# AnemometroWifi.net
KiCad netlist of a schematic drawn in EAGLE
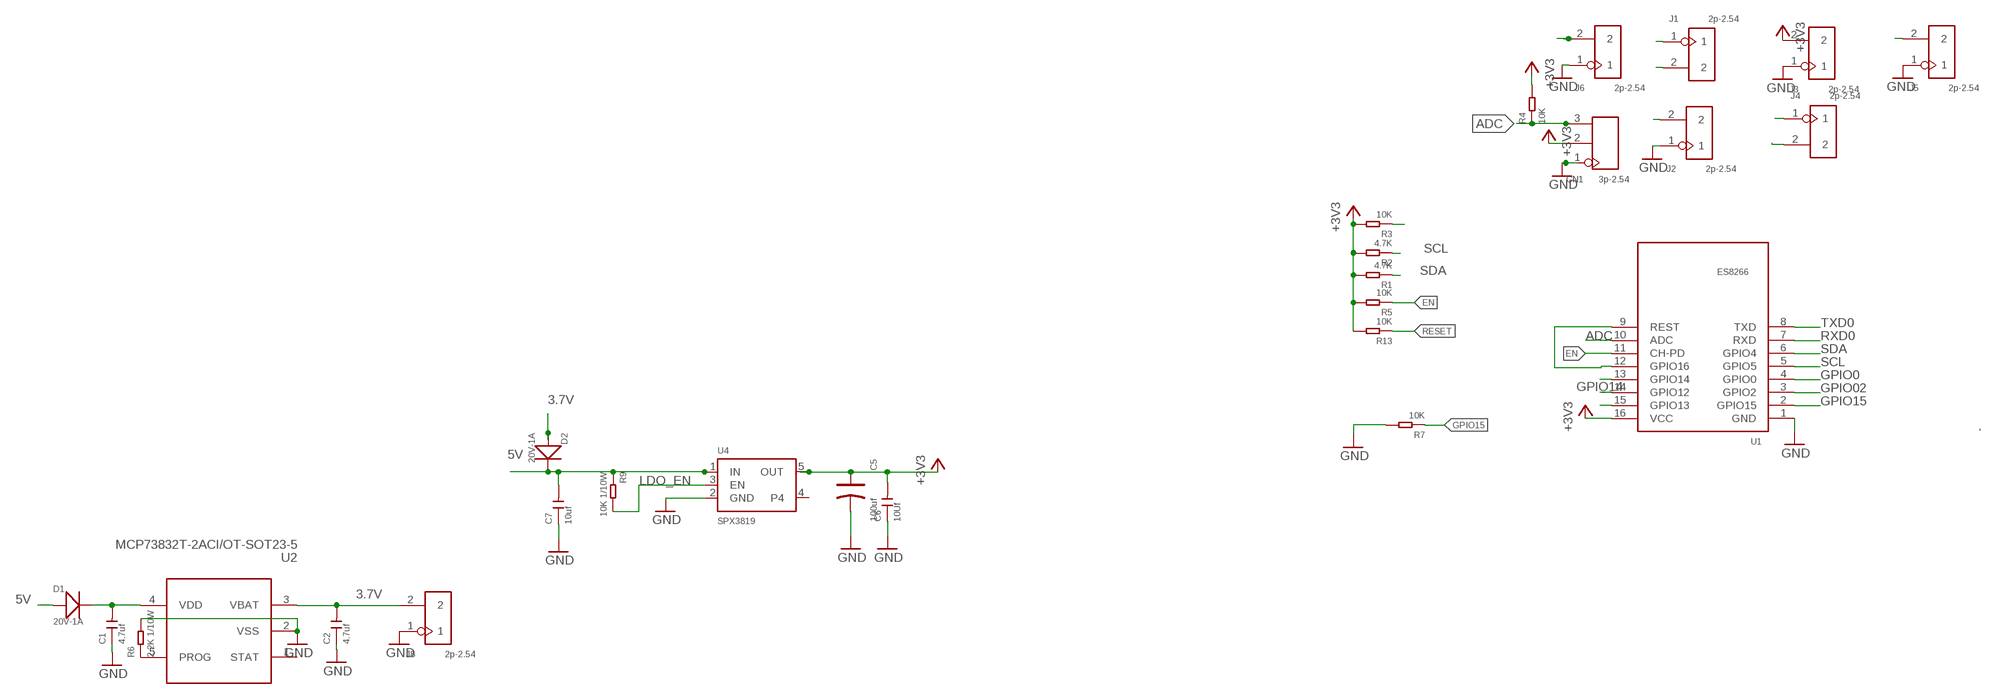
[diagram p0: schematic, sheet 1]

(export (version "E")
  (design (tool "Eeschema 10.0.6"))
  (components
    (comp (ref "C1")
      (value "4.7uf")
      (footprint "eagle-import:C0603")
      (fields (field (name "MPN") "CC0603KRX5R6BB475"))
      (libsource (lib "eagle-import") (part "CERAMIC-4.7UF-10V-10%-X5R(0603)"))
    )
    (comp (ref "C2")
      (value "4.7uf")
      (footprint "eagle-import:C0603")
      (fields (field (name "MPN") "CC0603KRX5R6BB475"))
      (libsource (lib "eagle-import") (part "CERAMIC-4.7UF-10V-10%-X5R(0603)"))
    )
    (comp (ref "C5")
      (value "100uf")
      (footprint "eagle-import:AVX-B")
      (fields (field (name "MPN") "TAJB107M010#NJ"))
      (libsource (lib "eagle-import") (part "TANTALUM-SMD-100UF-10V(AVX-B)"))
    )
    (comp (ref "C6")
      (value "10Uf")
      (footprint "eagle-import:C0603")
      (fields (field (name "MPN") "CC0603KRX7R9BB104"))
      (libsource (lib "eagle-import") (part "CERAMIC-100NF-50V-10%-X7R(0603)"))
    )
    (comp (ref "C7")
      (value "10uf")
      (footprint "eagle-import:C0805")
      (fields (field (name "MPN") "CC0805KKX5R8BB106"))
      (libsource (lib "eagle-import") (part "CERAMIC-10UF-25V-10%-X5R(0805)"))
    )
    (comp (ref "CN1")
      (value "3p-2.54")
      (footprint "eagle-import:H3-2.54")
      (libsource (lib "eagle-import") (part "DIP-BLACK-MALE-HEADER-VERT(3P-2.54)"))
    )
    (comp (ref "D1")
      (value "20V-1A")
      (footprint "eagle-import:SOD-123")
      (fields (field (name "MPN") "B5819W"))
      (libsource (lib "eagle-import") (part "SMD-DIODE-SCHOTTKY-20V-1A(SOD-123)"))
    )
    (comp (ref "D2")
      (value "20V-1A")
      (footprint "eagle-import:SOD-123")
      (fields (field (name "MPN") "B5819W"))
      (libsource (lib "eagle-import") (part "SMD-DIODE-SCHOTTKY-20V-1A(SOD-123)"))
    )
    (comp (ref "J1")
      (value "2p-2.54")
      (footprint "eagle-import:H2-2.54")
      (fields (field (name "MPN") "F185-1102A1BSYA1"))
      (libsource (lib "eagle-import") (part "DIP-BLACK-FEMALE-HEADER-VERT(2P-2.54)"))
    )
    (comp (ref "J2")
      (value "2p-2.54")
      (footprint "eagle-import:H2-2.54")
      (fields (field (name "MPN") "F185-1102A1BSYA1"))
      (libsource (lib "eagle-import") (part "DIP-BLACK-FEMALE-HEADER-VERT(2P-2.54)"))
    )
    (comp (ref "J3")
      (value "2p-2.54")
      (footprint "eagle-import:H2-2.54")
      (fields (field (name "MPN") "F185-1102A1BSYA1"))
      (libsource (lib "eagle-import") (part "DIP-BLACK-FEMALE-HEADER-VERT(2P-2.54)"))
    )
    (comp (ref "J4")
      (value "2p-2.54")
      (footprint "eagle-import:H2-2.54")
      (fields (field (name "MPN") "F185-1102A1BSYA1"))
      (libsource (lib "eagle-import") (part "DIP-BLACK-FEMALE-HEADER-VERT(2P-2.54)"))
    )
    (comp (ref "J5")
      (value "2p-2.54")
      (footprint "eagle-import:H2-2.54")
      (fields (field (name "MPN") "F185-1102A1BSYA1"))
      (libsource (lib "eagle-import") (part "DIP-BLACK-FEMALE-HEADER-VERT(2P-2.54)"))
    )
    (comp (ref "J6")
      (value "2p-2.54")
      (footprint "eagle-import:H2-2.54")
      (fields (field (name "MPN") "P125-1102A0BS116A1"))
      (libsource (lib "eagle-import") (part "DIP-BLACK-MALE-HEADER-VERT(2P-2.54)"))
    )
    (comp (ref "J8")
      (value "2p-2.54")
      (footprint "eagle-import:H2-2.54")
      (fields (field (name "MPN") "F185-1102A1BSYA1"))
      (libsource (lib "eagle-import") (part "DIP-BLACK-FEMALE-HEADER-VERT(2P-2.54)"))
    )
    (comp (ref "R1")
      (value "4.7K")
      (footprint "eagle-import:R0603")
      (fields (field (name "MPN") "RC0603JR-074K7L"))
      (libsource (lib "eagle-import") (part "SMD-RES-4.7K-5%-1/10W(0603)"))
    )
    (comp (ref "R2")
      (value "4.7K")
      (footprint "eagle-import:R0603")
      (fields (field (name "MPN") "RC0603JR-074K7L"))
      (libsource (lib "eagle-import") (part "SMD-RES-4.7K-5%-1/10W(0603)"))
    )
    (comp (ref "R3")
      (value "10K")
      (footprint "eagle-import:R0603")
      (fields (field (name "MPN") "RC0603JR-070RL"))
      (libsource (lib "eagle-import") (part "SMD-RES-0R-5%-1/10W(0603)"))
    )
    (comp (ref "R4")
      (value "10K")
      (footprint "eagle-import:R0603")
      (fields (field (name "MPN") "RC0603JR-070RL"))
      (libsource (lib "eagle-import") (part "SMD-RES-0R-5%-1/10W(0603)"))
    )
    (comp (ref "R5")
      (value "10K")
      (footprint "eagle-import:R0603")
      (fields (field (name "MPN") "RC0603JR-070RL"))
      (libsource (lib "eagle-import") (part "SMD-RES-0R-5%-1/10W(0603)"))
    )
    (comp (ref "R6")
      (value "2.2K 1/10W")
      (footprint "eagle-import:R0603")
      (fields (field (name "MPN") "RC0603FR-072K2L"))
      (libsource (lib "eagle-import") (part "SMD-RES-2.2K-1%-1/10W(0603)"))
    )
    (comp (ref "R7")
      (value "10K")
      (footprint "eagle-import:R0603")
      (fields (field (name "MPN") "RC0603JR-070RL"))
      (libsource (lib "eagle-import") (part "SMD-RES-0R-5%-1/10W(0603)"))
    )
    (comp (ref "R9")
      (value "10K 1/10W")
      (footprint "eagle-import:R0603")
      (fields (field (name "MPN") "RC0603JR-0710KL"))
      (libsource (lib "eagle-import") (part "SMD-RES-10K-5%-1/10W(0603)"))
    )
    (comp (ref "R13")
      (value "10K")
      (footprint "eagle-import:R0603")
      (fields (field (name "MPN") "RC0603JR-070RL"))
      (libsource (lib "eagle-import") (part "SMD-RES-0R-5%-1/10W(0603)"))
    )
    (comp (ref "U1")
      (value "ES8266")
      (footprint "eagle-import:LGA16-2.0-24X16MM")
      (libsource (lib "eagle-import") (part "MOUDLE-WIFI-ESP8266-AKX(16P-24X16MM)"))
    )
    (comp (ref "U2")
      (value "MCP73832T-2ACI/OT-SOT23-5")
      (footprint "eagle-import:SOT-23-5")
      (fields (field (name "MPN") "MCP73832T-2ACI/OT"))
      (libsource (lib "eagle-import") (part "PMIC-MCP73832T-2ACI/OT(SOT23-5)"))
    )
    (comp (ref "U4")
      (value "SPX3819")
      (footprint "eagle-import:SOT23-5")
      (libsource (lib "eagle-import") (part "VREG_SOT23-5"))
    )
  )
  (nets
    (net (code "1") (name "+3V3") (class "Default")
      (node (ref "C5") (pin "+") (pinfunction "+_+") (pintype "passive"))
      (node (ref "C6") (pin "2") (pinfunction "2_2") (pintype "passive"))
      (node (ref "CN1") (pin "2") (pinfunction "P$2_2") (pintype "bidirectional"))
      (node (ref "J3") (pin "2") (pinfunction "2_2") (pintype "bidirectional"))
      (node (ref "R1") (pin "2") (pinfunction "2_2") (pintype "passive"))
      (node (ref "R13") (pin "2") (pinfunction "2_2") (pintype "passive"))
      (node (ref "R2") (pin "2") (pinfunction "2_2") (pintype "passive"))
      (node (ref "R3") (pin "2") (pinfunction "2_2") (pintype "passive"))
      (node (ref "R4") (pin "2") (pinfunction "2_2") (pintype "passive"))
      (node (ref "R5") (pin "2") (pinfunction "2_2") (pintype "passive"))
      (node (ref "U1") (pin "16") (pinfunction "VCC_16") (pintype "bidirectional"))
      (node (ref "U4") (pin "5") (pinfunction "OUT_5") (pintype "power_in"))
    )
    (net (code "2") (name "/3.7V") (class "Default")
      (node (ref "C2") (pin "2") (pinfunction "2_2") (pintype "passive"))
      (node (ref "D2") (pin "+") (pinfunction "+_+") (pintype "passive"))
      (node (ref "J8") (pin "2") (pinfunction "2_2") (pintype "bidirectional"))
      (node (ref "U2") (pin "3") (pinfunction "VBAT_3") (pintype "output"))
    )
    (net (code "3") (name "/5V") (class "Default")
      (node (ref "C7") (pin "2") (pinfunction "2_2") (pintype "passive"))
      (node (ref "D1") (pin "+") (pinfunction "+_+") (pintype "passive"))
      (node (ref "D2") (pin "-") (pinfunction "-_-") (pintype "passive"))
      (node (ref "J5") (pin "2") (pinfunction "2_2") (pintype "bidirectional"))
      (node (ref "R9") (pin "1") (pinfunction "1_1") (pintype "passive"))
      (node (ref "U4") (pin "1") (pinfunction "IN_1") (pintype "power_in"))
    )
    (net (code "4") (name "/GPIO0") (class "Default")
      (node (ref "J6") (pin "2") (pinfunction "2_2") (pintype "bidirectional"))
      (node (ref "U1") (pin "4") (pinfunction "GPIO0_4") (pintype "bidirectional"))
    )
    (net (code "5") (name "/GPIO02") (class "Default")
      (node (ref "U1") (pin "3") (pinfunction "GPIO2_3") (pintype "bidirectional"))
    )
    (net (code "6") (name "/GPIO14") (class "Default")
      (node (ref "J2") (pin "2") (pinfunction "2_2") (pintype "bidirectional"))
      (node (ref "R3") (pin "1") (pinfunction "1_1") (pintype "passive"))
      (node (ref "U1") (pin "13") (pinfunction "GPIO14_13") (pintype "bidirectional"))
    )
    (net (code "7") (name "/LDO_EN") (class "Default")
      (node (ref "R9") (pin "2") (pinfunction "2_2") (pintype "passive"))
      (node (ref "U4") (pin "3") (pinfunction "EN_3") (pintype "input"))
    )
    (net (code "8") (name "/RXD0") (class "Default")
      (node (ref "J1") (pin "2") (pinfunction "2_2") (pintype "bidirectional"))
      (node (ref "U1") (pin "7") (pinfunction "RXD_7") (pintype "bidirectional"))
    )
    (net (code "9") (name "/SCL") (class "Default")
      (node (ref "J4") (pin "1") (pinfunction "1_1") (pintype "bidirectional"))
      (node (ref "R2") (pin "1") (pinfunction "1_1") (pintype "passive"))
      (node (ref "U1") (pin "5") (pinfunction "GPIO5_5") (pintype "bidirectional"))
    )
    (net (code "10") (name "/SDA") (class "Default")
      (node (ref "J4") (pin "2") (pinfunction "2_2") (pintype "bidirectional"))
      (node (ref "R1") (pin "1") (pinfunction "1_1") (pintype "passive"))
      (node (ref "U1") (pin "6") (pinfunction "GPIO4_6") (pintype "bidirectional"))
    )
    (net (code "11") (name "/TXD0") (class "Default")
      (node (ref "J1") (pin "1") (pinfunction "1_1") (pintype "bidirectional"))
      (node (ref "U1") (pin "8") (pinfunction "TXD_8") (pintype "bidirectional"))
    )
    (net (code "12") (name "ADC") (class "Default")
      (node (ref "CN1") (pin "3") (pinfunction "P$3_3") (pintype "bidirectional"))
      (node (ref "R4") (pin "1") (pinfunction "1_1") (pintype "passive"))
      (node (ref "U1") (pin "10") (pinfunction "ADC_10") (pintype "bidirectional"))
    )
    (net (code "13") (name "EN") (class "Default")
      (node (ref "R5") (pin "1") (pinfunction "1_1") (pintype "passive"))
      (node (ref "U1") (pin "11") (pinfunction "CH-PD_11") (pintype "bidirectional"))
    )
    (net (code "14") (name "GND") (class "Default")
      (node (ref "C1") (pin "1") (pinfunction "1_1") (pintype "passive"))
      (node (ref "C2") (pin "1") (pinfunction "1_1") (pintype "passive"))
      (node (ref "C5") (pin "-") (pinfunction "-_-") (pintype "passive"))
      (node (ref "C6") (pin "1") (pinfunction "1_1") (pintype "passive"))
      (node (ref "C7") (pin "1") (pinfunction "1_1") (pintype "passive"))
      (node (ref "CN1") (pin "1") (pinfunction "P$1_1") (pintype "bidirectional"))
      (node (ref "J2") (pin "1") (pinfunction "1_1") (pintype "bidirectional"))
      (node (ref "J3") (pin "1") (pinfunction "1_1") (pintype "bidirectional"))
      (node (ref "J5") (pin "1") (pinfunction "1_1") (pintype "bidirectional"))
      (node (ref "J6") (pin "1") (pinfunction "1_1") (pintype "bidirectional"))
      (node (ref "J8") (pin "1") (pinfunction "1_1") (pintype "bidirectional"))
      (node (ref "R6") (pin "2") (pinfunction "2_2") (pintype "passive"))
      (node (ref "R7") (pin "2") (pinfunction "2_2") (pintype "passive"))
      (node (ref "U1") (pin "1") (pinfunction "GND_1") (pintype "bidirectional"))
      (node (ref "U2") (pin "2") (pinfunction "VSS_2") (pintype "passive"))
      (node (ref "U4") (pin "2") (pinfunction "GND_2") (pintype "power_in"))
    )
    (net (code "15") (name "GPIO15") (class "Default")
      (node (ref "R7") (pin "1") (pinfunction "1_1") (pintype "passive"))
      (node (ref "U1") (pin "2") (pinfunction "GPIO15_2") (pintype "bidirectional"))
    )
    (net (code "16") (name "Net-(U2-PROG)") (class "Default")
      (node (ref "R6") (pin "1") (pinfunction "1_1") (pintype "passive"))
      (node (ref "U2") (pin "5") (pinfunction "PROG_5") (pintype "input"))
    )
    (net (code "17") (name "Net-(U2-VDD)") (class "Default")
      (node (ref "C1") (pin "2") (pinfunction "2_2") (pintype "passive"))
      (node (ref "D1") (pin "-") (pinfunction "-_-") (pintype "passive"))
      (node (ref "U2") (pin "4") (pinfunction "VDD_4") (pintype "input"))
    )
    (net (code "18") (name "RESET") (class "Default")
      (node (ref "R13") (pin "1") (pinfunction "1_1") (pintype "passive"))
      (node (ref "U1") (pin "12") (pinfunction "GPIO16_12") (pintype "bidirectional"))
      (node (ref "U1") (pin "9") (pinfunction "REST_9") (pintype "bidirectional"))
    )
    (net (code "19") (name "unconnected-(U1-GPIO12-Pad14)") (class "Default")
      (node (ref "U1") (pin "14") (pinfunction "GPIO12_14") (pintype "bidirectional"))
    )
    (net (code "20") (name "unconnected-(U1-GPIO13-Pad15)") (class "Default")
      (node (ref "U1") (pin "15") (pinfunction "GPIO13_15") (pintype "bidirectional"))
    )
    (net (code "21") (name "unconnected-(U2-STAT-Pad1)") (class "Default")
      (node (ref "U2") (pin "1") (pinfunction "STAT_1") (pintype "output"))
    )
    (net (code "22") (name "unconnected-(U4-P4-Pad4)") (class "Default")
      (node (ref "U4") (pin "4") (pinfunction "P4_4") (pintype "bidirectional"))
    )
  )
)
